# moth_v3_54mm_breakout.net
KiCad netlist of a schematic drawn in EAGLE
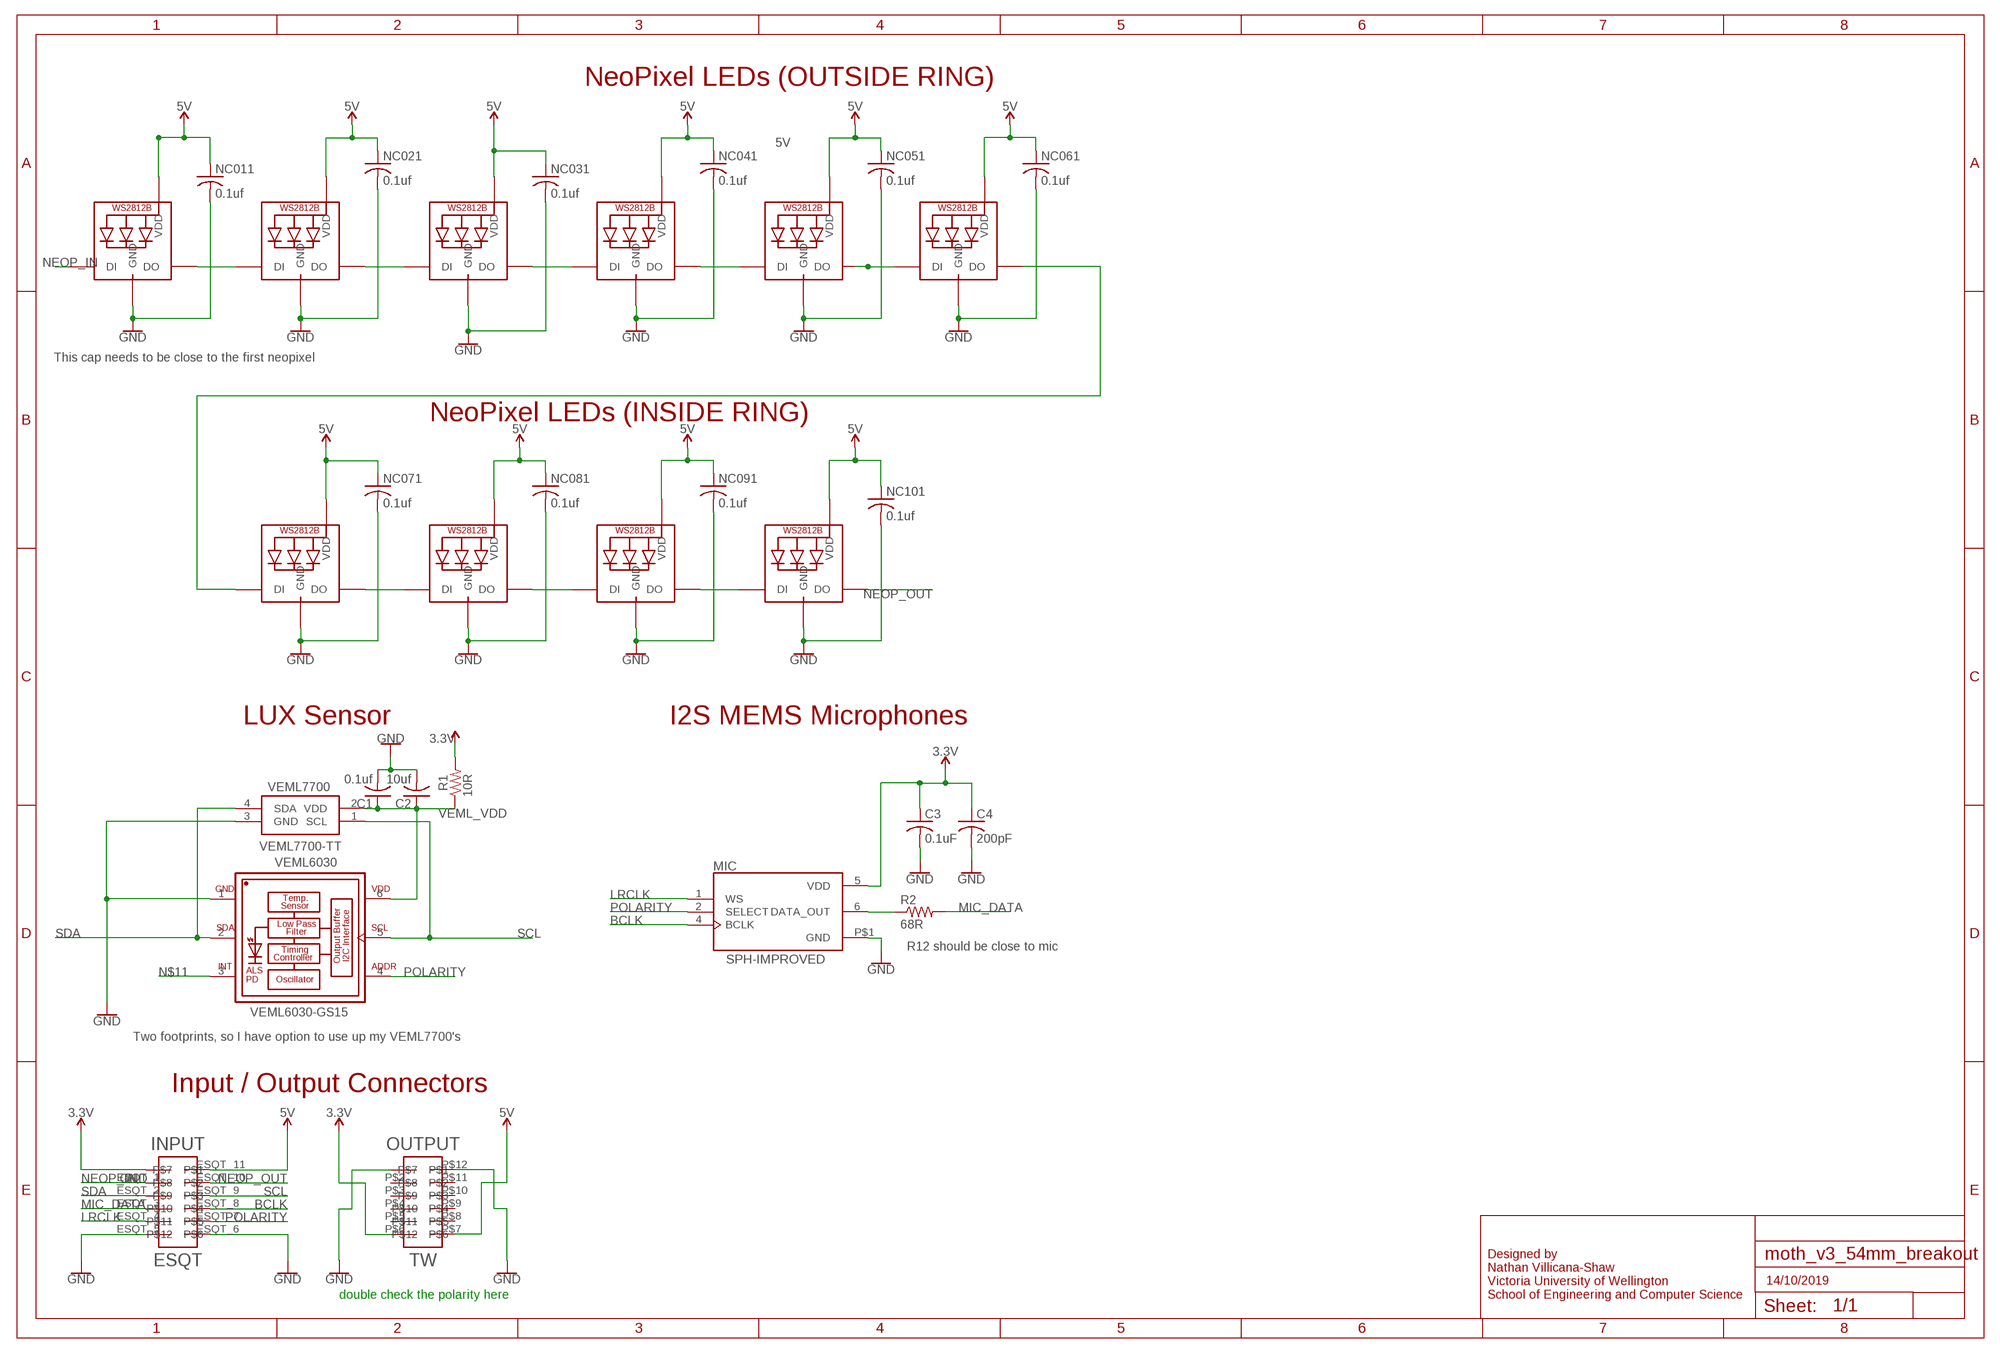
[diagram p0: schematic, sheet 1]

(export (version "E")
  (design (tool "Eeschema 10.0.6"))
  (components
    (comp (ref "C1")
      (value "0.1uf")
      (footprint "eagle-import:C0805")
      (libsource (lib "eagle-import") (part "C-USC0805"))
    )
    (comp (ref "C2")
      (value "10uf")
      (footprint "eagle-import:C0805")
      (libsource (lib "eagle-import") (part "C-USC0805"))
    )
    (comp (ref "C3")
      (value "0.1uF")
      (footprint "eagle-import:C0805")
      (libsource (lib "eagle-import") (part "C-USC0805"))
    )
    (comp (ref "C4")
      (value "200pF")
      (footprint "eagle-import:C0805")
      (libsource (lib "eagle-import") (part "C-USC0805"))
    )
    (comp (ref "INPUT")
      (value "ESQT")
      (footprint "eagle-import:SAMTEC_ESQT_2X6_THROUGH_HOLE")
      (libsource (lib "eagle-import") (part "SAMTEC_ESQT_2X6_THROUGH_HOLE"))
    )
    (comp (ref "MIC")
      (value "SPH-IMPROVED")
      (footprint "eagle-import:MIC_SPH0645LM4H-B_LARGER_RING")
      (libsource (lib "eagle-import") (part "SPH-IMPROVED"))
    )
    (comp (ref "NC011")
      (value "0.1uf")
      (footprint "eagle-import:C0805K")
      (libsource (lib "eagle-import") (part "C-USC0805K"))
    )
    (comp (ref "NC021")
      (value "0.1uf")
      (footprint "eagle-import:C0805K")
      (libsource (lib "eagle-import") (part "C-USC0805K"))
    )
    (comp (ref "NC031")
      (value "0.1uf")
      (footprint "eagle-import:C0805K")
      (libsource (lib "eagle-import") (part "C-USC0805K"))
    )
    (comp (ref "NC041")
      (value "0.1uf")
      (footprint "eagle-import:C0805K")
      (libsource (lib "eagle-import") (part "C-USC0805K"))
    )
    (comp (ref "NC051")
      (value "0.1uf")
      (footprint "eagle-import:C0805K")
      (libsource (lib "eagle-import") (part "C-USC0805K"))
    )
    (comp (ref "NC061")
      (value "0.1uf")
      (footprint "eagle-import:C0805K")
      (libsource (lib "eagle-import") (part "C-USC0805K"))
    )
    (comp (ref "NC071")
      (value "0.1uf")
      (footprint "eagle-import:C0805K")
      (libsource (lib "eagle-import") (part "C-USC0805K"))
    )
    (comp (ref "NC081")
      (value "0.1uf")
      (footprint "eagle-import:C0805K")
      (libsource (lib "eagle-import") (part "C-USC0805K"))
    )
    (comp (ref "NC091")
      (value "0.1uf")
      (footprint "eagle-import:C0805K")
      (libsource (lib "eagle-import") (part "C-USC0805K"))
    )
    (comp (ref "NC101")
      (value "0.1uf")
      (footprint "eagle-import:C0805K")
      (libsource (lib "eagle-import") (part "C-USC0805K"))
    )
    (comp (ref "NEO1")
      (value "WS2812B5050")
      (footprint "eagle-import:WS2812B")
      (libsource (lib "eagle-import") (part "WS2812B5050"))
    )
    (comp (ref "NEO2")
      (value "WS2812B5050")
      (footprint "eagle-import:WS2812B")
      (libsource (lib "eagle-import") (part "WS2812B5050"))
    )
    (comp (ref "NEO3")
      (value "WS2812B5050")
      (footprint "eagle-import:WS2812B")
      (libsource (lib "eagle-import") (part "WS2812B5050"))
    )
    (comp (ref "NEO4")
      (value "WS2812B5050")
      (footprint "eagle-import:WS2812B")
      (libsource (lib "eagle-import") (part "WS2812B5050"))
    )
    (comp (ref "NEO5")
      (value "WS2812B5050")
      (footprint "eagle-import:WS2812B")
      (libsource (lib "eagle-import") (part "WS2812B5050"))
    )
    (comp (ref "NEO6")
      (value "WS2812B5050")
      (footprint "eagle-import:WS2812B")
      (libsource (lib "eagle-import") (part "WS2812B5050"))
    )
    (comp (ref "NEO07")
      (value "WS2812B5050")
      (footprint "eagle-import:WS2812B")
      (libsource (lib "eagle-import") (part "WS2812B5050"))
    )
    (comp (ref "NEO08")
      (value "WS2812B5050")
      (footprint "eagle-import:WS2812B")
      (libsource (lib "eagle-import") (part "WS2812B5050"))
    )
    (comp (ref "NEO9")
      (value "WS2812B5050")
      (footprint "eagle-import:WS2812B")
      (libsource (lib "eagle-import") (part "WS2812B5050"))
    )
    (comp (ref "NEO10")
      (value "WS2812B5050")
      (footprint "eagle-import:WS2812B")
      (libsource (lib "eagle-import") (part "WS2812B5050"))
    )
    (comp (ref "OUTPUT")
      (value "TW")
      (footprint "eagle-import:SAMTEC_TW_2X6")
      (libsource (lib "eagle-import") (part "SAMTEC_TW_2X6_WITH_STABLE"))
    )
    (comp (ref "R1")
      (value "10R")
      (footprint "eagle-import:R0805")
      (libsource (lib "eagle-import") (part "audio amplifier example_970892_R-US_R0805"))
    )
    (comp (ref "R2")
      (value "68R")
      (footprint "eagle-import:M0805")
      (libsource (lib "eagle-import") (part "R-US_M0805"))
    )
    (comp (ref "VEML6030")
      (value "VEML6030-GS15")
      (footprint "eagle-import:VISHAY_VEML6030_2X2X0.87")
      (fields (field (name "MF") "Vishay Semiconductor"))
      (libsource (lib "eagle-import") (part "VEML6030-GS15"))
    )
    (comp (ref "VEML7700")
      (value "VEML7700-TT")
      (footprint "eagle-import:VEML7700")
      (fields (field (name "MOUSER_PART_NUMBER") "78-VEML7700-TT") (field (name "RS_PART_NUMBER") "1226791P"))
      (libsource (lib "eagle-import") (part "VEML7700-TT"))
    )
  )
  (nets
    (net (code "1") (name "/BCLK") (class "Default")
      (node (ref "INPUT") (pin "ESQT_8") (pinfunction "P$10_ESQT_8") (pintype "bidirectional"))
      (node (ref "MIC") (pin "4") (pinfunction "BCLK_4") (pintype "input"))
    )
    (net (code "2") (name "/LRCLK") (class "Default")
      (node (ref "INPUT") (pin "ESQT_4") (pinfunction "P$5_ESQT_4") (pintype "bidirectional"))
      (node (ref "MIC") (pin "1") (pinfunction "WS_1") (pintype "input"))
    )
    (net (code "3") (name "/MIC_DATA") (class "Default")
      (node (ref "INPUT") (pin "ESQT_3") (pinfunction "P$4_ESQT_3") (pintype "bidirectional"))
      (node (ref "R2") (pin "2") (pinfunction "2_2") (pintype "passive"))
    )
    (net (code "4") (name "/N$11") (class "Default")
      (node (ref "VEML6030") (pin "3") (pinfunction "INT_3") (pintype "output"))
    )
    (net (code "5") (name "/NEOP_IN") (class "Default")
      (node (ref "INPUT") (pin "ESQT_1") (pinfunction "P$2_ESQT_1") (pintype "bidirectional"))
      (node (ref "NEO1") (pin "4-DIN") (pinfunction "DI_4-DIN") (pintype "input"))
    )
    (net (code "6") (name "/NEOP_OUT") (class "Default")
      (node (ref "INPUT") (pin "ESQT_10") (pinfunction "P$8_ESQT_10") (pintype "bidirectional"))
      (node (ref "NEO10") (pin "2-DOUT") (pinfunction "DO_2-DOUT") (pintype "output"))
    )
    (net (code "7") (name "/POLARITY") (class "Default")
      (node (ref "INPUT") (pin "ESQT_7") (pinfunction "P$11_ESQT_7") (pintype "bidirectional"))
      (node (ref "MIC") (pin "2") (pinfunction "SELECT_2") (pintype "input"))
      (node (ref "VEML6030") (pin "4") (pinfunction "ADDR_4") (pintype "bidirectional"))
    )
    (net (code "8") (name "/SCL") (class "Default")
      (node (ref "INPUT") (pin "ESQT_9") (pinfunction "P$9_ESQT_9") (pintype "bidirectional"))
      (node (ref "VEML6030") (pin "5") (pinfunction "SCL_5") (pintype "input"))
      (node (ref "VEML7700") (pin "1") (pinfunction "SCL_1") (pintype "bidirectional"))
    )
    (net (code "9") (name "/SDA") (class "Default")
      (node (ref "INPUT") (pin "ESQT_2") (pinfunction "P$3_ESQT_2") (pintype "bidirectional"))
      (node (ref "VEML6030") (pin "2") (pinfunction "SDA_2") (pintype "bidirectional"))
      (node (ref "VEML7700") (pin "4") (pinfunction "SDA_4") (pintype "bidirectional"))
    )
    (net (code "10") (name "/VEML_VDD") (class "Default")
      (node (ref "C1") (pin "1") (pinfunction "1_1") (pintype "passive"))
      (node (ref "C2") (pin "1") (pinfunction "1_1") (pintype "passive"))
      (node (ref "R1") (pin "1") (pinfunction "1_1") (pintype "passive"))
      (node (ref "VEML6030") (pin "6") (pinfunction "VDD_6") (pintype "power_in"))
      (node (ref "VEML7700") (pin "2") (pinfunction "VDD_2") (pintype "bidirectional"))
    )
    (net (code "11") (name "3.3V") (class "Default")
      (node (ref "C3") (pin "1") (pinfunction "1_1") (pintype "passive"))
      (node (ref "C4") (pin "1") (pinfunction "1_1") (pintype "passive"))
      (node (ref "INPUT") (pin "ESQT_0") (pinfunction "P$1_ESQT_0") (pintype "bidirectional"))
      (node (ref "MIC") (pin "5") (pinfunction "VDD_5") (pintype "power_in"))
      (node (ref "OUTPUT") (pin "P$6") (pinfunction "P$6_P$6") (pintype "bidirectional"))
      (node (ref "R1") (pin "2") (pinfunction "2_2") (pintype "passive"))
    )
    (net (code "12") (name "5V") (class "Default")
      (node (ref "INPUT") (pin "ESQT_11") (pinfunction "P$7_ESQT_11") (pintype "bidirectional"))
      (node (ref "NC011") (pin "1") (pinfunction "1_1") (pintype "passive"))
      (node (ref "NC021") (pin "1") (pinfunction "1_1") (pintype "passive"))
      (node (ref "NC031") (pin "1") (pinfunction "1_1") (pintype "passive"))
      (node (ref "NC041") (pin "1") (pinfunction "1_1") (pintype "passive"))
      (node (ref "NC051") (pin "1") (pinfunction "1_1") (pintype "passive"))
      (node (ref "NC061") (pin "1") (pinfunction "1_1") (pintype "passive"))
      (node (ref "NC071") (pin "1") (pinfunction "1_1") (pintype "passive"))
      (node (ref "NC081") (pin "1") (pinfunction "1_1") (pintype "passive"))
      (node (ref "NC091") (pin "1") (pinfunction "1_1") (pintype "passive"))
      (node (ref "NC101") (pin "1") (pinfunction "1_1") (pintype "passive"))
      (node (ref "NEO07") (pin "1-VDD") (pinfunction "VDD_1-VDD") (pintype "power_in"))
      (node (ref "NEO08") (pin "1-VDD") (pinfunction "VDD_1-VDD") (pintype "power_in"))
      (node (ref "NEO1") (pin "1-VDD") (pinfunction "VDD_1-VDD") (pintype "power_in"))
      (node (ref "NEO10") (pin "1-VDD") (pinfunction "VDD_1-VDD") (pintype "power_in"))
      (node (ref "NEO2") (pin "1-VDD") (pinfunction "VDD_1-VDD") (pintype "power_in"))
      (node (ref "NEO3") (pin "1-VDD") (pinfunction "VDD_1-VDD") (pintype "power_in"))
      (node (ref "NEO4") (pin "1-VDD") (pinfunction "VDD_1-VDD") (pintype "power_in"))
      (node (ref "NEO5") (pin "1-VDD") (pinfunction "VDD_1-VDD") (pintype "power_in"))
      (node (ref "NEO6") (pin "1-VDD") (pinfunction "VDD_1-VDD") (pintype "power_in"))
      (node (ref "NEO9") (pin "1-VDD") (pinfunction "VDD_1-VDD") (pintype "power_in"))
      (node (ref "OUTPUT") (pin "P$7") (pinfunction "P$12_P$7") (pintype "bidirectional"))
    )
    (net (code "13") (name "GND") (class "Default")
      (node (ref "C1") (pin "2") (pinfunction "2_2") (pintype "passive"))
      (node (ref "C2") (pin "2") (pinfunction "2_2") (pintype "passive"))
      (node (ref "C3") (pin "2") (pinfunction "2_2") (pintype "passive"))
      (node (ref "C4") (pin "2") (pinfunction "2_2") (pintype "passive"))
      (node (ref "INPUT") (pin "ESQT_5") (pinfunction "P$6_ESQT_5") (pintype "bidirectional"))
      (node (ref "INPUT") (pin "ESQT_6") (pinfunction "P$12_ESQT_6") (pintype "bidirectional"))
      (node (ref "MIC") (pin "P$1") (pinfunction "GND_P$1") (pintype "power_in"))
      (node (ref "NC011") (pin "2") (pinfunction "2_2") (pintype "passive"))
      (node (ref "NC021") (pin "2") (pinfunction "2_2") (pintype "passive"))
      (node (ref "NC031") (pin "2") (pinfunction "2_2") (pintype "passive"))
      (node (ref "NC041") (pin "2") (pinfunction "2_2") (pintype "passive"))
      (node (ref "NC051") (pin "2") (pinfunction "2_2") (pintype "passive"))
      (node (ref "NC061") (pin "2") (pinfunction "2_2") (pintype "passive"))
      (node (ref "NC071") (pin "2") (pinfunction "2_2") (pintype "passive"))
      (node (ref "NC081") (pin "2") (pinfunction "2_2") (pintype "passive"))
      (node (ref "NC091") (pin "2") (pinfunction "2_2") (pintype "passive"))
      (node (ref "NC101") (pin "2") (pinfunction "2_2") (pintype "passive"))
      (node (ref "NEO07") (pin "3-GND") (pinfunction "GND_3-GND") (pintype "power_in"))
      (node (ref "NEO08") (pin "3-GND") (pinfunction "GND_3-GND") (pintype "power_in"))
      (node (ref "NEO1") (pin "3-GND") (pinfunction "GND_3-GND") (pintype "power_in"))
      (node (ref "NEO10") (pin "3-GND") (pinfunction "GND_3-GND") (pintype "power_in"))
      (node (ref "NEO2") (pin "3-GND") (pinfunction "GND_3-GND") (pintype "power_in"))
      (node (ref "NEO3") (pin "3-GND") (pinfunction "GND_3-GND") (pintype "power_in"))
      (node (ref "NEO4") (pin "3-GND") (pinfunction "GND_3-GND") (pintype "power_in"))
      (node (ref "NEO5") (pin "3-GND") (pinfunction "GND_3-GND") (pintype "power_in"))
      (node (ref "NEO6") (pin "3-GND") (pinfunction "GND_3-GND") (pintype "power_in"))
      (node (ref "NEO9") (pin "3-GND") (pinfunction "GND_3-GND") (pintype "power_in"))
      (node (ref "OUTPUT") (pin "P$1") (pinfunction "P$1_P$1") (pintype "bidirectional"))
      (node (ref "OUTPUT") (pin "P$12") (pinfunction "P$7_P$12") (pintype "bidirectional"))
      (node (ref "VEML6030") (pin "1") (pinfunction "GND_1") (pintype "power_in"))
      (node (ref "VEML7700") (pin "3") (pinfunction "GND_3") (pintype "bidirectional"))
    )
    (net (code "14") (name "Net-(MIC-DATA_OUT)") (class "Default")
      (node (ref "MIC") (pin "6") (pinfunction "DATA_OUT_6") (pintype "output"))
      (node (ref "R2") (pin "1") (pinfunction "1_1") (pintype "passive"))
    )
    (net (code "15") (name "Net-(NEO1-DO)") (class "Default")
      (node (ref "NEO1") (pin "2-DOUT") (pinfunction "DO_2-DOUT") (pintype "output"))
      (node (ref "NEO2") (pin "4-DIN") (pinfunction "DI_4-DIN") (pintype "input"))
    )
    (net (code "16") (name "Net-(NEO2-DO)") (class "Default")
      (node (ref "NEO2") (pin "2-DOUT") (pinfunction "DO_2-DOUT") (pintype "output"))
      (node (ref "NEO3") (pin "4-DIN") (pinfunction "DI_4-DIN") (pintype "input"))
    )
    (net (code "17") (name "Net-(NEO3-DO)") (class "Default")
      (node (ref "NEO3") (pin "2-DOUT") (pinfunction "DO_2-DOUT") (pintype "output"))
      (node (ref "NEO4") (pin "4-DIN") (pinfunction "DI_4-DIN") (pintype "input"))
    )
    (net (code "18") (name "Net-(NEO4-DO)") (class "Default")
      (node (ref "NEO4") (pin "2-DOUT") (pinfunction "DO_2-DOUT") (pintype "output"))
      (node (ref "NEO5") (pin "4-DIN") (pinfunction "DI_4-DIN") (pintype "input"))
    )
    (net (code "19") (name "Net-(NEO5-DO)") (class "Default")
      (node (ref "NEO5") (pin "2-DOUT") (pinfunction "DO_2-DOUT") (pintype "output"))
      (node (ref "NEO6") (pin "4-DIN") (pinfunction "DI_4-DIN") (pintype "input"))
    )
    (net (code "20") (name "Net-(NEO07-DI)") (class "Default")
      (node (ref "NEO07") (pin "4-DIN") (pinfunction "DI_4-DIN") (pintype "input"))
      (node (ref "NEO6") (pin "2-DOUT") (pinfunction "DO_2-DOUT") (pintype "output"))
    )
    (net (code "21") (name "Net-(NEO07-DO)") (class "Default")
      (node (ref "NEO07") (pin "2-DOUT") (pinfunction "DO_2-DOUT") (pintype "output"))
      (node (ref "NEO08") (pin "4-DIN") (pinfunction "DI_4-DIN") (pintype "input"))
    )
    (net (code "22") (name "Net-(NEO08-DO)") (class "Default")
      (node (ref "NEO08") (pin "2-DOUT") (pinfunction "DO_2-DOUT") (pintype "output"))
      (node (ref "NEO9") (pin "4-DIN") (pinfunction "DI_4-DIN") (pintype "input"))
    )
    (net (code "23") (name "Net-(NEO10-DI)") (class "Default")
      (node (ref "NEO10") (pin "4-DIN") (pinfunction "DI_4-DIN") (pintype "input"))
      (node (ref "NEO9") (pin "2-DOUT") (pinfunction "DO_2-DOUT") (pintype "output"))
    )
    (net (code "24") (name "unconnected-(OUTPUT-P$8-PadP$11)") (class "Default")
      (node (ref "OUTPUT") (pin "P$11") (pinfunction "P$8_P$11") (pintype "bidirectional"))
    )
    (net (code "25") (name "unconnected-(OUTPUT-P$9-PadP$10)") (class "Default")
      (node (ref "OUTPUT") (pin "P$10") (pinfunction "P$9_P$10") (pintype "bidirectional"))
    )
    (net (code "26") (name "unconnected-(OUTPUT-P$10-PadP$9)") (class "Default")
      (node (ref "OUTPUT") (pin "P$9") (pinfunction "P$10_P$9") (pintype "bidirectional"))
    )
    (net (code "27") (name "unconnected-(OUTPUT-P$11-PadP$8)") (class "Default")
      (node (ref "OUTPUT") (pin "P$8") (pinfunction "P$11_P$8") (pintype "bidirectional"))
    )
    (net (code "28") (name "unconnected-(OUTPUT-PadP$2)") (class "Default")
      (node (ref "OUTPUT") (pin "P$2") (pinfunction "P$2_P$2") (pintype "bidirectional"))
    )
    (net (code "29") (name "unconnected-(OUTPUT-PadP$3)") (class "Default")
      (node (ref "OUTPUT") (pin "P$3") (pinfunction "P$3_P$3") (pintype "bidirectional"))
    )
    (net (code "30") (name "unconnected-(OUTPUT-PadP$4)") (class "Default")
      (node (ref "OUTPUT") (pin "P$4") (pinfunction "P$4_P$4") (pintype "bidirectional"))
    )
    (net (code "31") (name "unconnected-(OUTPUT-PadP$5)") (class "Default")
      (node (ref "OUTPUT") (pin "P$5") (pinfunction "P$5_P$5") (pintype "bidirectional"))
    )
  )
)
